# SH4_-_5V_VICOR_DCDC.net
KiCad netlist of a schematic drawn in Altium Designer
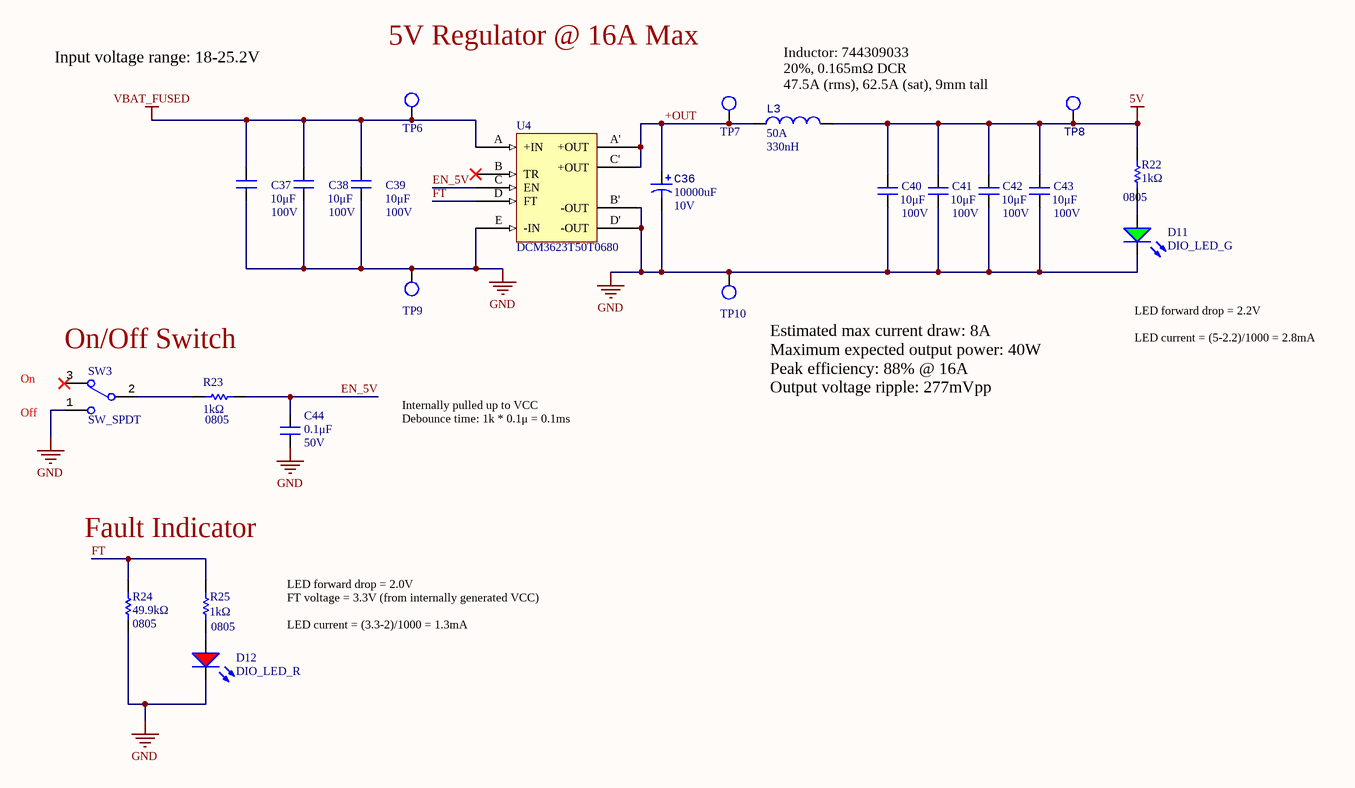
[diagram p0: SH4 - 5V VICOR DCDC.SchDoc]

(export (version "E")
  (design (tool "Eeschema 10.0.6"))
  (components
    (comp (ref "C36")
      (value "URS1A103MHD1TN")
      (footprint "CAP_UBY_18X25_NC")
      (description "CAP ALUM 10000UF 20% 10V RADIAL")
      (fields
        (field (name "TOLERANCE") "20%")
        (field (name "CAPACITANCE") "10000uF")
        (field (name "VOLTAGE RATING") "10V")
      )
      (libsource (lib "UWRT_Schematic_Library_2020") (part "URS1A103MHD1TN"))
    )
    (comp (ref "C37")
      (value "10μF")
      (footprint "CAP1210")
      (description "CAP CER 10uF 100V X7S 10% 1210")
      (fields
        (field (name "TOLERANCE") "10%")
        (field (name "VOLTAGE RATING") "100V")
        (field (name "Comment") "CAP_10uF_100V_1210")
      )
      (libsource (lib "UWRT_Schematic_Library_2020") (part "CAP_10uF_100V_1210"))
    )
    (comp (ref "C38")
      (value "10μF")
      (footprint "CAP1210")
      (description "CAP CER 10uF 100V X7S 10% 1210")
      (fields
        (field (name "TOLERANCE") "10%")
        (field (name "VOLTAGE RATING") "100V")
        (field (name "Comment") "CAP_10uF_100V_1210")
      )
      (libsource (lib "UWRT_Schematic_Library_2020") (part "CAP_10uF_100V_1210"))
    )
    (comp (ref "C39")
      (value "10μF")
      (footprint "CAP1210")
      (description "CAP CER 10uF 100V X7S 10% 1210")
      (fields
        (field (name "TOLERANCE") "10%")
        (field (name "VOLTAGE RATING") "100V")
        (field (name "Comment") "CAP_10uF_100V_1210")
      )
      (libsource (lib "UWRT_Schematic_Library_2020") (part "CAP_10uF_100V_1210"))
    )
    (comp (ref "C40")
      (value "10μF")
      (footprint "CAP1210")
      (description "CAP CER 10uF 100V X7S 10% 1210")
      (fields
        (field (name "VOLTAGE RATING") "100V")
        (field (name "TOLERANCE") "10%")
        (field (name "Comment") "CAP_10uF_100V_1210")
      )
      (libsource (lib "UWRT_Schematic_Library_2020") (part "CAP_10uF_100V_1210"))
    )
    (comp (ref "C41")
      (value "10μF")
      (footprint "CAP1210")
      (description "CAP CER 10uF 100V X7S 10% 1210")
      (fields
        (field (name "VOLTAGE RATING") "100V")
        (field (name "TOLERANCE") "10%")
        (field (name "Comment") "CAP_10uF_100V_1210")
      )
      (libsource (lib "UWRT_Schematic_Library_2020") (part "CAP_10uF_100V_1210"))
    )
    (comp (ref "C42")
      (value "10μF")
      (footprint "CAP1210")
      (description "CAP CER 10uF 100V X7S 10% 1210")
      (fields
        (field (name "VOLTAGE RATING") "100V")
        (field (name "TOLERANCE") "10%")
        (field (name "Comment") "CAP_10uF_100V_1210")
      )
      (libsource (lib "UWRT_Schematic_Library_2020") (part "CAP_10uF_100V_1210"))
    )
    (comp (ref "C43")
      (value "10μF")
      (footprint "CAP1210")
      (description "CAP CER 10uF 100V X7S 10% 1210")
      (fields
        (field (name "VOLTAGE RATING") "100V")
        (field (name "TOLERANCE") "10%")
        (field (name "Comment") "CAP_10uF_100V_1210")
      )
      (libsource (lib "UWRT_Schematic_Library_2020") (part "CAP_10uF_100V_1210"))
    )
    (comp (ref "C44")
      (value "0.1μF")
      (footprint "CAP2012")
      (description "CAP CER 0.1UF 50V X7R 0805")
      (fields
        (field (name "VOLTAGE RATING") "50V")
        (field (name "TOLERANCE") "10%")
        (field (name "LCSC PART #") "C49678")
      )
      (libsource (lib "UWRT_Schematic_Library_2020") (part "CAP_0.1uF_50V_0805"))
    )
    (comp (ref "D11")
      (value "DIO_LED_G")
      (footprint "LED_0805_GREEN")
      (description "LED GREEN DIFFUSED 0805 SMD")
      (libsource (lib "UWRT_Schematic_Library_2020") (part "DIO_LED_G"))
    )
    (comp (ref "D12")
      (value "DIO_LED_R")
      (footprint "LED_0805_RED")
      (description "LED RED DIFFUSED 0805 SMD")
      (libsource (lib "UWRT_Schematic_Library_2020") (part "DIO_LED_R"))
    )
    (comp (ref "L3")
      (value "744309033")
      (footprint "WE-HCM 1390")
      (description "IND 330NH 47.5A 0.165 MOHM")
      (fields
        (field (name "TOLERANCE") "20%")
        (field (name "MAX DC CURRENT") "50A")
        (field (name "INDUCTANCE") "330nH")
      )
      (libsource (lib "UWRT_Schematic_Library_2020") (part "744309033"))
    )
    (comp (ref "R22")
      (value "RES_1kΩ_0805_1%")
      (footprint "RESC0805")
      (description "RES 1K OHM 1% 1/8W 0805")
      (fields
        (field (name "TOLERANCE") "1%")
        (field (name "RESISTANCE") "1kΩ")
        (field (name "LCSC PART #") "C17513")
        (field (name "PACKAGE/FOOTPRINT") "0805")
      )
      (libsource (lib "UWRT_Schematic_Library_2020") (part "RES_1kΩ_0805_1%"))
    )
    (comp (ref "R23")
      (value "RES_1kΩ_0805_1%")
      (footprint "RESC0805")
      (description "RES 1K OHM 1% 1/8W 0805")
      (fields
        (field (name "TOLERANCE") "1%")
        (field (name "RESISTANCE") "1kΩ")
        (field (name "LCSC PART #") "C17513")
        (field (name "PACKAGE/FOOTPRINT") "0805")
      )
      (libsource (lib "UWRT_Schematic_Library_2020") (part "RES_1kΩ_0805_1%"))
    )
    (comp (ref "R24")
      (value "RES_49.9kΩ_0805_1%")
      (footprint "RESC0805")
      (description "RES 49.9K OHM 1% 1/8W 0805")
      (fields
        (field (name "TOLERANCE") "1%")
        (field (name "RESISTANCE") "49.9kΩ")
        (field (name "LCSC PART #") "C17719")
        (field (name "PACKAGE/FOOTPRINT") "0805")
      )
      (libsource (lib "UWRT_Schematic_Library_2020") (part "RES_49.9kΩ_0805_1%"))
    )
    (comp (ref "R25")
      (value "RES_1kΩ_0805_1%")
      (footprint "RESC0805")
      (description "RES 1K OHM 1% 1/8W 0805")
      (fields
        (field (name "TOLERANCE") "1%")
        (field (name "RESISTANCE") "1kΩ")
        (field (name "LCSC PART #") "C17513")
        (field (name "PACKAGE/FOOTPRINT") "0805")
      )
      (libsource (lib "UWRT_Schematic_Library_2020") (part "RES_1kΩ_0805_1%"))
    )
    (comp (ref "SW3")
      (value "SW_SPDT")
      (footprint "100SP1T1B4M2QE")
      (description "SWITCH TOGGLE SPDT 5A 120V")
      (libsource (lib "UWRT_Schematic_Library_2020") (part "SW_SPDT"))
    )
    (comp (ref "TP6")
      (value "TESTPOINT_LOOP")
      (footprint "TESTPOINT_LOOP")
      (description "PC TEST POINT MINIATURE WHITE")
      (libsource (lib "UWRT_Schematic_Library_2020") (part "TESTPOINT_LOOP"))
    )
    (comp (ref "TP7")
      (value "TESTPOINT_LOOP")
      (footprint "TESTPOINT_LOOP")
      (description "PC TEST POINT MINIATURE WHITE")
      (libsource (lib "UWRT_Schematic_Library_2020") (part "TESTPOINT_LOOP"))
    )
    (comp (ref "TP8")
      (value "TESTPOINT_LOOP")
      (footprint "TESTPOINT_LOOP")
      (description "PC TEST POINT MINIATURE WHITE")
      (libsource (lib "UWRT_Schematic_Library_2020") (part "TESTPOINT_LOOP"))
    )
    (comp (ref "TP9")
      (value "TESTPOINT_LOOP")
      (footprint "TESTPOINT_LOOP")
      (description "PC TEST POINT MINIATURE WHITE")
      (libsource (lib "UWRT_Schematic_Library_2020") (part "TESTPOINT_LOOP"))
    )
    (comp (ref "TP10")
      (value "TESTPOINT_LOOP")
      (footprint "TESTPOINT_LOOP")
      (description "PC TEST POINT MINIATURE WHITE")
      (libsource (lib "UWRT_Schematic_Library_2020") (part "TESTPOINT_LOOP"))
    )
    (comp (ref "U4")
      (value "DCM3623T50T0680")
      (footprint "DCM3623T50T0680")
      (description "DC DC CONVERTER 5V 80W")
      (libsource (lib "UWRT_Schematic_Library_2020") (part "DCM3623T50T0680"))
    )
  )
  (nets
    (net (code "1") (name "/+OUT") (class "Default")
      (node (ref "C36") (pin "1") (pinfunction "1_1") (pintype "passive"))
      (node (ref "L3") (pin "1") (pinfunction "1_1") (pintype "passive"))
      (node (ref "TP7") (pin "1") (pintype "passive"))
      (node (ref "U4") (pin "A'") (pinfunction "+OUT_A'") (pintype "passive"))
      (node (ref "U4") (pin "C'") (pinfunction "+OUT_C'") (pintype "passive"))
    )
    (net (code "2") (name "/EN_5V") (class "Default")
      (node (ref "C44") (pin "2") (pinfunction "2_2") (pintype "passive"))
      (node (ref "R23") (pin "2") (pinfunction "2_2") (pintype "passive"))
      (node (ref "U4") (pin "C") (pinfunction "EN_C") (pintype "input"))
    )
    (net (code "3") (name "/FT") (class "Default")
      (node (ref "R24") (pin "1") (pinfunction "1_1") (pintype "passive"))
      (node (ref "R25") (pin "2") (pinfunction "2_2") (pintype "passive"))
      (node (ref "U4") (pin "D") (pinfunction "FT_D") (pintype "input"))
    )
    (net (code "4") (name "5V") (class "Default")
      (node (ref "C40") (pin "2") (pinfunction "2_2") (pintype "passive"))
      (node (ref "C41") (pin "2") (pinfunction "2_2") (pintype "passive"))
      (node (ref "C42") (pin "2") (pinfunction "2_2") (pintype "passive"))
      (node (ref "C43") (pin "2") (pinfunction "2_2") (pintype "passive"))
      (node (ref "L3") (pin "2") (pinfunction "2_2") (pintype "passive"))
      (node (ref "R22") (pin "2") (pinfunction "2_2") (pintype "passive"))
      (node (ref "TP8") (pin "1") (pintype "passive"))
    )
    (net (code "5") (name "GND") (class "Default")
      (node (ref "C36") (pin "2") (pinfunction "2_2") (pintype "passive"))
      (node (ref "C37") (pin "1") (pinfunction "1_1") (pintype "passive"))
      (node (ref "C38") (pin "1") (pinfunction "1_1") (pintype "passive"))
      (node (ref "C39") (pin "1") (pinfunction "1_1") (pintype "passive"))
      (node (ref "C40") (pin "1") (pinfunction "1_1") (pintype "passive"))
      (node (ref "C41") (pin "1") (pinfunction "1_1") (pintype "passive"))
      (node (ref "C42") (pin "1") (pinfunction "1_1") (pintype "passive"))
      (node (ref "C43") (pin "1") (pinfunction "1_1") (pintype "passive"))
      (node (ref "C44") (pin "1") (pinfunction "1_1") (pintype "passive"))
      (node (ref "D11") (pin "2") (pinfunction "K_2") (pintype "passive"))
      (node (ref "D12") (pin "2") (pinfunction "K_2") (pintype "passive"))
      (node (ref "R24") (pin "2") (pinfunction "2_2") (pintype "passive"))
      (node (ref "SW3") (pin "1") (pinfunction "1_1") (pintype "passive"))
      (node (ref "TP10") (pin "1") (pintype "passive"))
      (node (ref "TP9") (pin "1") (pintype "passive"))
      (node (ref "U4") (pin "B'") (pinfunction "-OUT_B'") (pintype "passive"))
      (node (ref "U4") (pin "D'") (pinfunction "-OUT_D'") (pintype "passive"))
      (node (ref "U4") (pin "E") (pinfunction "-IN_E") (pintype "input"))
    )
    (net (code "6") (name "Net-(D11-A)") (class "Default")
      (node (ref "D11") (pin "1") (pinfunction "A_1") (pintype "passive"))
      (node (ref "R22") (pin "1") (pinfunction "1_1") (pintype "passive"))
    )
    (net (code "7") (name "Net-(D12-A)") (class "Default")
      (node (ref "D12") (pin "1") (pinfunction "A_1") (pintype "passive"))
      (node (ref "R25") (pin "1") (pinfunction "1_1") (pintype "passive"))
    )
    (net (code "8") (name "Net-(R23-Pad1)") (class "Default")
      (node (ref "R23") (pin "1") (pinfunction "1_1") (pintype "passive"))
      (node (ref "SW3") (pin "2") (pinfunction "2_2") (pintype "passive"))
    )
    (net (code "9") (name "VBAT_FUSED") (class "Default")
      (node (ref "C37") (pin "2") (pinfunction "2_2") (pintype "passive"))
      (node (ref "C38") (pin "2") (pinfunction "2_2") (pintype "passive"))
      (node (ref "C39") (pin "2") (pinfunction "2_2") (pintype "passive"))
      (node (ref "TP6") (pin "1") (pintype "passive"))
      (node (ref "U4") (pin "A") (pinfunction "+IN_A") (pintype "input"))
    )
    (net (code "10") (name "unconnected-(SW3-Pad3)") (class "Default")
      (node (ref "SW3") (pin "3") (pinfunction "3_3") (pintype "passive+no_connect"))
    )
    (net (code "11") (name "unconnected-(U4-TR-PadB)") (class "Default")
      (node (ref "U4") (pin "B") (pinfunction "TR_B") (pintype "input+no_connect"))
    )
  )
)
